# 180_schematic_5_layer.net
KiCad netlist of a schematic drawn in EAGLE
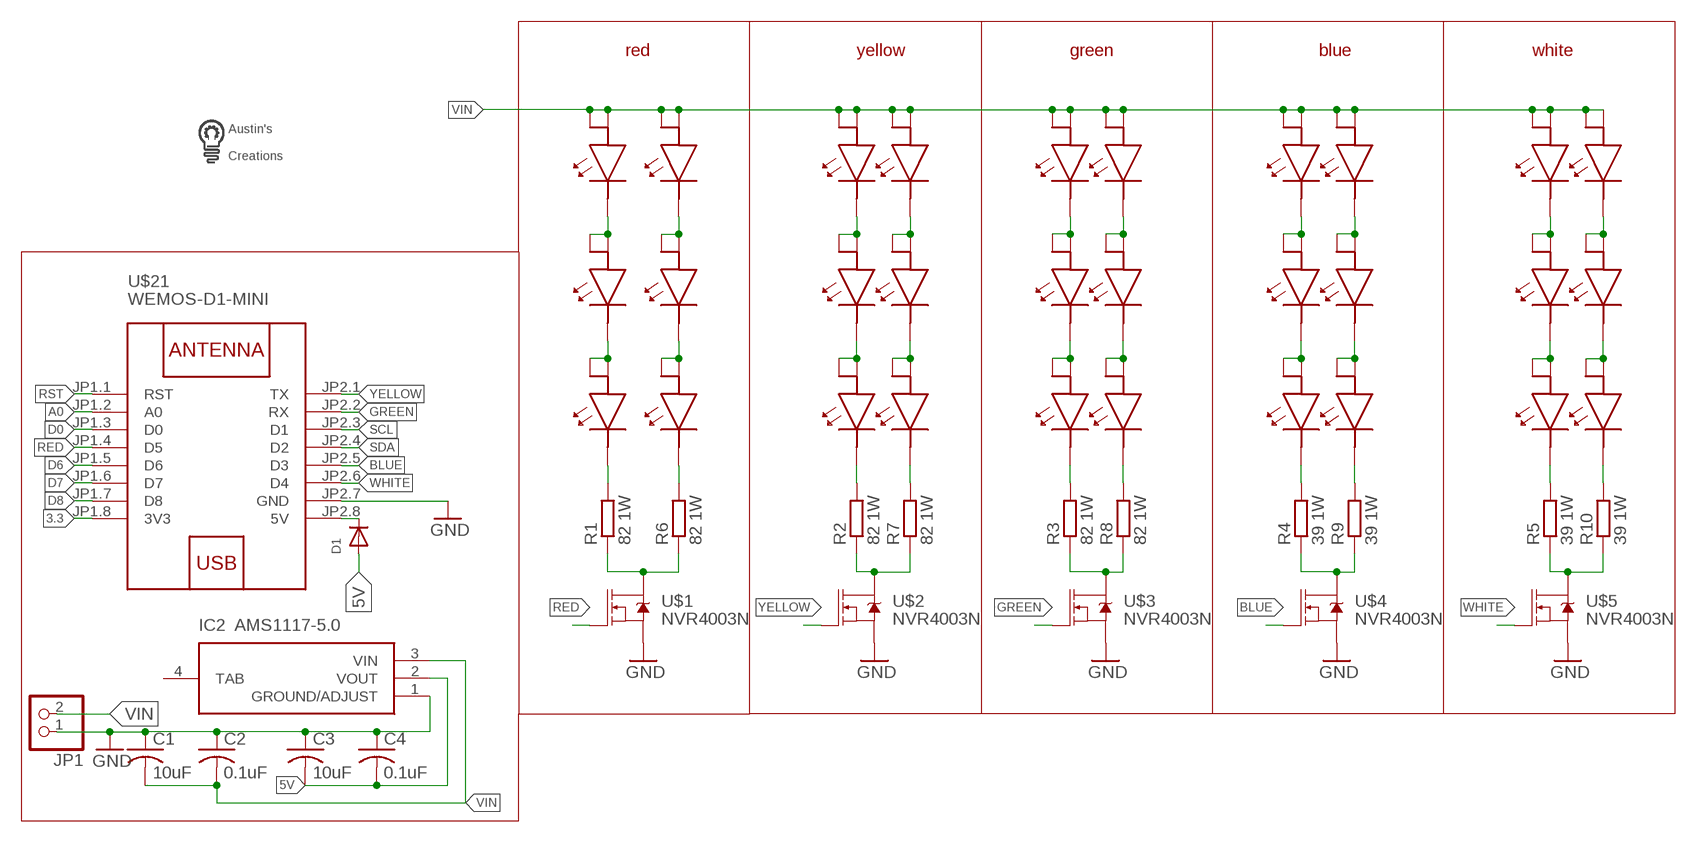
[diagram p0: schematic, sheet 1]

(export (version "E")
  (design (tool "Eeschema 10.0.6"))
  (components
    (comp (ref "C1")
      (value "10uF")
      (footprint "eagle-import:C0603")
      (libsource (lib "eagle-import") (part "C-USC0603"))
    )
    (comp (ref "C2")
      (value "0.1uF")
      (footprint "eagle-import:C0603")
      (libsource (lib "eagle-import") (part "C-USC0603"))
    )
    (comp (ref "C3")
      (value "10uF")
      (footprint "eagle-import:C0603")
      (libsource (lib "eagle-import") (part "C-USC0603"))
    )
    (comp (ref "C4")
      (value "0.1uF")
      (footprint "eagle-import:C0603")
      (libsource (lib "eagle-import") (part "C-USC0603"))
    )
    (comp (ref "D1")
      (value "DIODESOD-123")
      (footprint "eagle-import:SOD-123")
      (libsource (lib "eagle-import") (part "DIODESOD-123"))
    )
    (comp (ref "IC2")
      (value "AMS1117-5.0")
      (footprint "eagle-import:SOT229P700X180-4N")
      (libsource (lib "eagle-import") (part "AMS1117-5.0"))
    )
    (comp (ref "JP1")
      (value "PINHD-1X2")
      (footprint "eagle-import:1X02")
      (libsource (lib "eagle-import") (part "PINHD-1X2"))
    )
    (comp (ref "R1")
      (value "82 1W")
      (footprint "eagle-import:R2010")
      (libsource (lib "eagle-import") (part "R-EU_R2010"))
    )
    (comp (ref "R2")
      (value "82 1W")
      (footprint "eagle-import:R2010")
      (libsource (lib "eagle-import") (part "R-EU_R2010"))
    )
    (comp (ref "R3")
      (value "82 1W")
      (footprint "eagle-import:R2010")
      (libsource (lib "eagle-import") (part "R-EU_R2010"))
    )
    (comp (ref "R4")
      (value "39 1W")
      (footprint "eagle-import:R2010")
      (libsource (lib "eagle-import") (part "R-EU_R2010"))
    )
    (comp (ref "R5")
      (value "39 1W")
      (footprint "eagle-import:R2010")
      (libsource (lib "eagle-import") (part "R-EU_R2010"))
    )
    (comp (ref "R6")
      (value "82 1W")
      (footprint "eagle-import:R2010")
      (libsource (lib "eagle-import") (part "R-EU_R2010"))
    )
    (comp (ref "R7")
      (value "82 1W")
      (footprint "eagle-import:R2010")
      (libsource (lib "eagle-import") (part "R-EU_R2010"))
    )
    (comp (ref "R8")
      (value "82 1W")
      (footprint "eagle-import:R2010")
      (libsource (lib "eagle-import") (part "R-EU_R2010"))
    )
    (comp (ref "R9")
      (value "39 1W")
      (footprint "eagle-import:R2010")
      (libsource (lib "eagle-import") (part "R-EU_R2010"))
    )
    (comp (ref "R10")
      (value "39 1W")
      (footprint "eagle-import:R2010")
      (libsource (lib "eagle-import") (part "R-EU_R2010"))
    )
    (comp (ref "U$1")
      (value "NVR4003N")
      (footprint "eagle-import:SOT23")
      (libsource (lib "eagle-import") (part "NVR4003N"))
    )
    (comp (ref "U$2")
      (value "NVR4003N")
      (footprint "eagle-import:SOT23")
      (libsource (lib "eagle-import") (part "NVR4003N"))
    )
    (comp (ref "U$3")
      (value "NVR4003N")
      (footprint "eagle-import:SOT23")
      (libsource (lib "eagle-import") (part "NVR4003N"))
    )
    (comp (ref "U$4")
      (value "NVR4003N")
      (footprint "eagle-import:SOT23")
      (libsource (lib "eagle-import") (part "NVR4003N"))
    )
    (comp (ref "U$5")
      (value "NVR4003N")
      (footprint "eagle-import:SOT23")
      (libsource (lib "eagle-import") (part "NVR4003N"))
    )
    (comp (ref "U$6")
      (value "5730LED")
      (footprint "eagle-import:5730LED")
      (libsource (lib "eagle-import") (part "5730LED"))
    )
    (comp (ref "U$7")
      (value "5730LED")
      (footprint "eagle-import:5730LED")
      (libsource (lib "eagle-import") (part "5730LED"))
    )
    (comp (ref "U$8")
      (value "5730LED")
      (footprint "eagle-import:5730LED")
      (libsource (lib "eagle-import") (part "5730LED"))
    )
    (comp (ref "U$9")
      (value "5730LED")
      (footprint "eagle-import:5730LED")
      (libsource (lib "eagle-import") (part "5730LED"))
    )
    (comp (ref "U$10")
      (value "5730LED")
      (footprint "eagle-import:5730LED")
      (libsource (lib "eagle-import") (part "5730LED"))
    )
    (comp (ref "U$11")
      (value "5730LED")
      (footprint "eagle-import:5730LED")
      (libsource (lib "eagle-import") (part "5730LED"))
    )
    (comp (ref "U$12")
      (value "5730LED")
      (footprint "eagle-import:5730LED")
      (libsource (lib "eagle-import") (part "5730LED"))
    )
    (comp (ref "U$13")
      (value "5730LED")
      (footprint "eagle-import:5730LED")
      (libsource (lib "eagle-import") (part "5730LED"))
    )
    (comp (ref "U$14")
      (value "5730LED")
      (footprint "eagle-import:5730LED")
      (libsource (lib "eagle-import") (part "5730LED"))
    )
    (comp (ref "U$15")
      (value "5730LED")
      (footprint "eagle-import:5730LED")
      (libsource (lib "eagle-import") (part "5730LED"))
    )
    (comp (ref "U$16")
      (value "5730LED")
      (footprint "eagle-import:5730LED")
      (libsource (lib "eagle-import") (part "5730LED"))
    )
    (comp (ref "U$17")
      (value "5730LED")
      (footprint "eagle-import:5730LED")
      (libsource (lib "eagle-import") (part "5730LED"))
    )
    (comp (ref "U$18")
      (value "5730LED")
      (footprint "eagle-import:5730LED")
      (libsource (lib "eagle-import") (part "5730LED"))
    )
    (comp (ref "U$19")
      (value "5730LED")
      (footprint "eagle-import:5730LED")
      (libsource (lib "eagle-import") (part "5730LED"))
    )
    (comp (ref "U$20")
      (value "5730LED")
      (footprint "eagle-import:5730LED")
      (libsource (lib "eagle-import") (part "5730LED"))
    )
    (comp (ref "U$21")
      (value "WEMOS-D1-MINI")
      (footprint "eagle-import:WEMOS-D1-MINI")
      (libsource (lib "eagle-import") (part "WEMOS-D1-MINI"))
    )
    (comp (ref "U$22")
      (value "LOGO")
      (footprint "eagle-import:LOGO")
      (libsource (lib "eagle-import") (part "LOGO"))
    )
    (comp (ref "U$23")
      (value "5730LED")
      (footprint "eagle-import:5730LED")
      (libsource (lib "eagle-import") (part "5730LED"))
    )
    (comp (ref "U$24")
      (value "5730LED")
      (footprint "eagle-import:5730LED")
      (libsource (lib "eagle-import") (part "5730LED"))
    )
    (comp (ref "U$25")
      (value "5730LED")
      (footprint "eagle-import:5730LED")
      (libsource (lib "eagle-import") (part "5730LED"))
    )
    (comp (ref "U$26")
      (value "5730LED")
      (footprint "eagle-import:5730LED")
      (libsource (lib "eagle-import") (part "5730LED"))
    )
    (comp (ref "U$27")
      (value "5730LED")
      (footprint "eagle-import:5730LED")
      (libsource (lib "eagle-import") (part "5730LED"))
    )
    (comp (ref "U$28")
      (value "5730LED")
      (footprint "eagle-import:5730LED")
      (libsource (lib "eagle-import") (part "5730LED"))
    )
    (comp (ref "U$29")
      (value "5730LED")
      (footprint "eagle-import:5730LED")
      (libsource (lib "eagle-import") (part "5730LED"))
    )
    (comp (ref "U$30")
      (value "5730LED")
      (footprint "eagle-import:5730LED")
      (libsource (lib "eagle-import") (part "5730LED"))
    )
    (comp (ref "U$31")
      (value "5730LED")
      (footprint "eagle-import:5730LED")
      (libsource (lib "eagle-import") (part "5730LED"))
    )
    (comp (ref "U$32")
      (value "5730LED")
      (footprint "eagle-import:5730LED")
      (libsource (lib "eagle-import") (part "5730LED"))
    )
    (comp (ref "U$33")
      (value "5730LED")
      (footprint "eagle-import:5730LED")
      (libsource (lib "eagle-import") (part "5730LED"))
    )
    (comp (ref "U$34")
      (value "5730LED")
      (footprint "eagle-import:5730LED")
      (libsource (lib "eagle-import") (part "5730LED"))
    )
    (comp (ref "U$35")
      (value "5730LED")
      (footprint "eagle-import:5730LED")
      (libsource (lib "eagle-import") (part "5730LED"))
    )
    (comp (ref "U$36")
      (value "5730LED")
      (footprint "eagle-import:5730LED")
      (libsource (lib "eagle-import") (part "5730LED"))
    )
    (comp (ref "U$37")
      (value "5730LED")
      (footprint "eagle-import:5730LED")
      (libsource (lib "eagle-import") (part "5730LED"))
    )
  )
  (nets
    (net (code "1") (name "3.3") (class "Default")
      (node (ref "U$21") (pin "JP1.8") (pinfunction "3V3_JP1.8") (pintype "power_in"))
    )
    (net (code "2") (name "5V") (class "Default")
      (node (ref "C3") (pin "2") (pinfunction "2_2") (pintype "passive"))
      (node (ref "C4") (pin "2") (pinfunction "2_2") (pintype "passive"))
      (node (ref "D1") (pin "A") (pinfunction "A_A") (pintype "passive"))
      (node (ref "IC2") (pin "2") (pinfunction "VOUT_2") (pintype "bidirectional"))
    )
    (net (code "3") (name "A0") (class "Default")
      (node (ref "U$21") (pin "JP1.2") (pinfunction "A0_JP1.2") (pintype "bidirectional"))
    )
    (net (code "4") (name "BLUE") (class "Default")
      (node (ref "U$21") (pin "JP2.5") (pinfunction "D3_JP2.5") (pintype "bidirectional"))
      (node (ref "U$4") (pin "2") (pinfunction "G_2") (pintype "bidirectional"))
    )
    (net (code "5") (name "D0") (class "Default")
      (node (ref "U$21") (pin "JP1.3") (pinfunction "D0_JP1.3") (pintype "bidirectional"))
    )
    (net (code "6") (name "D6") (class "Default")
      (node (ref "U$21") (pin "JP1.5") (pinfunction "D6_JP1.5") (pintype "bidirectional"))
    )
    (net (code "7") (name "D7") (class "Default")
      (node (ref "U$21") (pin "JP1.6") (pinfunction "D7_JP1.6") (pintype "bidirectional"))
    )
    (net (code "8") (name "D8") (class "Default")
      (node (ref "U$21") (pin "JP1.7") (pinfunction "D8_JP1.7") (pintype "bidirectional"))
    )
    (net (code "9") (name "GND") (class "Default")
      (node (ref "C1") (pin "1") (pinfunction "1_1") (pintype "passive"))
      (node (ref "C2") (pin "1") (pinfunction "1_1") (pintype "passive"))
      (node (ref "C3") (pin "1") (pinfunction "1_1") (pintype "passive"))
      (node (ref "C4") (pin "1") (pinfunction "1_1") (pintype "passive"))
      (node (ref "IC2") (pin "1") (pinfunction "GROUND/ADJUST_1") (pintype "bidirectional"))
      (node (ref "JP1") (pin "1") (pinfunction "1_1") (pintype "passive"))
      (node (ref "U$1") (pin "3") (pinfunction "S_3") (pintype "bidirectional"))
      (node (ref "U$2") (pin "3") (pinfunction "S_3") (pintype "bidirectional"))
      (node (ref "U$21") (pin "JP2.7") (pinfunction "GND_JP2.7") (pintype "power_in"))
      (node (ref "U$3") (pin "3") (pinfunction "S_3") (pintype "bidirectional"))
      (node (ref "U$4") (pin "3") (pinfunction "S_3") (pintype "bidirectional"))
      (node (ref "U$5") (pin "3") (pinfunction "S_3") (pintype "bidirectional"))
    )
    (net (code "10") (name "GREEN") (class "Default")
      (node (ref "U$21") (pin "JP2.2") (pinfunction "RX_JP2.2") (pintype "bidirectional"))
      (node (ref "U$3") (pin "2") (pinfunction "G_2") (pintype "bidirectional"))
    )
    (net (code "11") (name "Net-(R1-Pad2)") (class "Default")
      (node (ref "R1") (pin "2") (pinfunction "2_2") (pintype "passive"))
      (node (ref "U$8") (pin "P$2") (pinfunction "P$2_P$2") (pintype "bidirectional"))
    )
    (net (code "12") (name "Net-(R2-Pad2)") (class "Default")
      (node (ref "R2") (pin "2") (pinfunction "2_2") (pintype "passive"))
      (node (ref "U$11") (pin "P$2") (pinfunction "P$2_P$2") (pintype "bidirectional"))
    )
    (net (code "13") (name "Net-(R3-Pad2)") (class "Default")
      (node (ref "R3") (pin "2") (pinfunction "2_2") (pintype "passive"))
      (node (ref "U$14") (pin "P$2") (pinfunction "P$2_P$2") (pintype "bidirectional"))
    )
    (net (code "14") (name "Net-(R4-Pad2)") (class "Default")
      (node (ref "R4") (pin "2") (pinfunction "2_2") (pintype "passive"))
      (node (ref "U$17") (pin "P$2") (pinfunction "P$2_P$2") (pintype "bidirectional"))
    )
    (net (code "15") (name "Net-(R5-Pad2)") (class "Default")
      (node (ref "R5") (pin "2") (pinfunction "2_2") (pintype "passive"))
      (node (ref "U$20") (pin "P$2") (pinfunction "P$2_P$2") (pintype "bidirectional"))
    )
    (net (code "16") (name "Net-(R6-Pad2)") (class "Default")
      (node (ref "R6") (pin "2") (pinfunction "2_2") (pintype "passive"))
      (node (ref "U$25") (pin "P$2") (pinfunction "P$2_P$2") (pintype "bidirectional"))
    )
    (net (code "17") (name "Net-(R7-Pad2)") (class "Default")
      (node (ref "R7") (pin "2") (pinfunction "2_2") (pintype "passive"))
      (node (ref "U$28") (pin "P$2") (pinfunction "P$2_P$2") (pintype "bidirectional"))
    )
    (net (code "18") (name "Net-(R8-Pad2)") (class "Default")
      (node (ref "R8") (pin "2") (pinfunction "2_2") (pintype "passive"))
      (node (ref "U$31") (pin "P$2") (pinfunction "P$2_P$2") (pintype "bidirectional"))
    )
    (net (code "19") (name "Net-(R9-Pad2)") (class "Default")
      (node (ref "R9") (pin "2") (pinfunction "2_2") (pintype "passive"))
      (node (ref "U$34") (pin "P$2") (pinfunction "P$2_P$2") (pintype "bidirectional"))
    )
    (net (code "20") (name "Net-(R10-Pad2)") (class "Default")
      (node (ref "R10") (pin "2") (pinfunction "2_2") (pintype "passive"))
      (node (ref "U$37") (pin "P$2") (pinfunction "P$2_P$2") (pintype "bidirectional"))
    )
    (net (code "21") (name "Net-(U$1-D)") (class "Default")
      (node (ref "R1") (pin "1") (pinfunction "1_1") (pintype "passive"))
      (node (ref "R6") (pin "1") (pinfunction "1_1") (pintype "passive"))
      (node (ref "U$1") (pin "1") (pinfunction "D_1") (pintype "bidirectional"))
    )
    (net (code "22") (name "Net-(U$2-D)") (class "Default")
      (node (ref "R2") (pin "1") (pinfunction "1_1") (pintype "passive"))
      (node (ref "R7") (pin "1") (pinfunction "1_1") (pintype "passive"))
      (node (ref "U$2") (pin "1") (pinfunction "D_1") (pintype "bidirectional"))
    )
    (net (code "23") (name "Net-(U$3-D)") (class "Default")
      (node (ref "R3") (pin "1") (pinfunction "1_1") (pintype "passive"))
      (node (ref "R8") (pin "1") (pinfunction "1_1") (pintype "passive"))
      (node (ref "U$3") (pin "1") (pinfunction "D_1") (pintype "bidirectional"))
    )
    (net (code "24") (name "Net-(U$4-D)") (class "Default")
      (node (ref "R4") (pin "1") (pinfunction "1_1") (pintype "passive"))
      (node (ref "R9") (pin "1") (pinfunction "1_1") (pintype "passive"))
      (node (ref "U$4") (pin "1") (pinfunction "D_1") (pintype "bidirectional"))
    )
    (net (code "25") (name "Net-(U$5-D)") (class "Default")
      (node (ref "R10") (pin "1") (pinfunction "1_1") (pintype "passive"))
      (node (ref "R5") (pin "1") (pinfunction "1_1") (pintype "passive"))
      (node (ref "U$5") (pin "1") (pinfunction "D_1") (pintype "bidirectional"))
    )
    (net (code "26") (name "Net-(U$6-PadP$2)") (class "Default")
      (node (ref "U$6") (pin "P$2") (pinfunction "P$2_P$2") (pintype "bidirectional"))
      (node (ref "U$7") (pin "P$1") (pinfunction "P$1_P$1") (pintype "bidirectional"))
      (node (ref "U$7") (pin "P$3") (pinfunction "P$3_P$3") (pintype "bidirectional"))
    )
    (net (code "27") (name "Net-(U$7-PadP$2)") (class "Default")
      (node (ref "U$7") (pin "P$2") (pinfunction "P$2_P$2") (pintype "bidirectional"))
      (node (ref "U$8") (pin "P$1") (pinfunction "P$1_P$1") (pintype "bidirectional"))
      (node (ref "U$8") (pin "P$3") (pinfunction "P$3_P$3") (pintype "bidirectional"))
    )
    (net (code "28") (name "Net-(U$10-PadP$1)") (class "Default")
      (node (ref "U$10") (pin "P$1") (pinfunction "P$1_P$1") (pintype "bidirectional"))
      (node (ref "U$10") (pin "P$3") (pinfunction "P$3_P$3") (pintype "bidirectional"))
      (node (ref "U$9") (pin "P$2") (pinfunction "P$2_P$2") (pintype "bidirectional"))
    )
    (net (code "29") (name "Net-(U$10-PadP$2)") (class "Default")
      (node (ref "U$10") (pin "P$2") (pinfunction "P$2_P$2") (pintype "bidirectional"))
      (node (ref "U$11") (pin "P$1") (pinfunction "P$1_P$1") (pintype "bidirectional"))
      (node (ref "U$11") (pin "P$3") (pinfunction "P$3_P$3") (pintype "bidirectional"))
    )
    (net (code "30") (name "Net-(U$12-PadP$2)") (class "Default")
      (node (ref "U$12") (pin "P$2") (pinfunction "P$2_P$2") (pintype "bidirectional"))
      (node (ref "U$13") (pin "P$1") (pinfunction "P$1_P$1") (pintype "bidirectional"))
      (node (ref "U$13") (pin "P$3") (pinfunction "P$3_P$3") (pintype "bidirectional"))
    )
    (net (code "31") (name "Net-(U$13-PadP$2)") (class "Default")
      (node (ref "U$13") (pin "P$2") (pinfunction "P$2_P$2") (pintype "bidirectional"))
      (node (ref "U$14") (pin "P$1") (pinfunction "P$1_P$1") (pintype "bidirectional"))
      (node (ref "U$14") (pin "P$3") (pinfunction "P$3_P$3") (pintype "bidirectional"))
    )
    (net (code "32") (name "Net-(U$15-PadP$2)") (class "Default")
      (node (ref "U$15") (pin "P$2") (pinfunction "P$2_P$2") (pintype "bidirectional"))
      (node (ref "U$16") (pin "P$1") (pinfunction "P$1_P$1") (pintype "bidirectional"))
      (node (ref "U$16") (pin "P$3") (pinfunction "P$3_P$3") (pintype "bidirectional"))
    )
    (net (code "33") (name "Net-(U$16-PadP$2)") (class "Default")
      (node (ref "U$16") (pin "P$2") (pinfunction "P$2_P$2") (pintype "bidirectional"))
      (node (ref "U$17") (pin "P$1") (pinfunction "P$1_P$1") (pintype "bidirectional"))
      (node (ref "U$17") (pin "P$3") (pinfunction "P$3_P$3") (pintype "bidirectional"))
    )
    (net (code "34") (name "Net-(U$18-PadP$2)") (class "Default")
      (node (ref "U$18") (pin "P$2") (pinfunction "P$2_P$2") (pintype "bidirectional"))
      (node (ref "U$19") (pin "P$1") (pinfunction "P$1_P$1") (pintype "bidirectional"))
      (node (ref "U$19") (pin "P$3") (pinfunction "P$3_P$3") (pintype "bidirectional"))
    )
    (net (code "35") (name "Net-(U$19-PadP$2)") (class "Default")
      (node (ref "U$19") (pin "P$2") (pinfunction "P$2_P$2") (pintype "bidirectional"))
      (node (ref "U$20") (pin "P$1") (pinfunction "P$1_P$1") (pintype "bidirectional"))
      (node (ref "U$20") (pin "P$3") (pinfunction "P$3_P$3") (pintype "bidirectional"))
    )
    (net (code "36") (name "Net-(U$21-5V)") (class "Default")
      (node (ref "D1") (pin "C") (pinfunction "C_C") (pintype "passive"))
      (node (ref "U$21") (pin "JP2.8") (pinfunction "5V_JP2.8") (pintype "power_in"))
    )
    (net (code "37") (name "Net-(U$23-PadP$2)") (class "Default")
      (node (ref "U$23") (pin "P$2") (pinfunction "P$2_P$2") (pintype "bidirectional"))
      (node (ref "U$24") (pin "P$1") (pinfunction "P$1_P$1") (pintype "bidirectional"))
      (node (ref "U$24") (pin "P$3") (pinfunction "P$3_P$3") (pintype "bidirectional"))
    )
    (net (code "38") (name "Net-(U$24-PadP$2)") (class "Default")
      (node (ref "U$24") (pin "P$2") (pinfunction "P$2_P$2") (pintype "bidirectional"))
      (node (ref "U$25") (pin "P$1") (pinfunction "P$1_P$1") (pintype "bidirectional"))
      (node (ref "U$25") (pin "P$3") (pinfunction "P$3_P$3") (pintype "bidirectional"))
    )
    (net (code "39") (name "Net-(U$26-PadP$2)") (class "Default")
      (node (ref "U$26") (pin "P$2") (pinfunction "P$2_P$2") (pintype "bidirectional"))
      (node (ref "U$27") (pin "P$1") (pinfunction "P$1_P$1") (pintype "bidirectional"))
      (node (ref "U$27") (pin "P$3") (pinfunction "P$3_P$3") (pintype "bidirectional"))
    )
    (net (code "40") (name "Net-(U$27-PadP$2)") (class "Default")
      (node (ref "U$27") (pin "P$2") (pinfunction "P$2_P$2") (pintype "bidirectional"))
      (node (ref "U$28") (pin "P$1") (pinfunction "P$1_P$1") (pintype "bidirectional"))
      (node (ref "U$28") (pin "P$3") (pinfunction "P$3_P$3") (pintype "bidirectional"))
    )
    (net (code "41") (name "Net-(U$29-PadP$2)") (class "Default")
      (node (ref "U$29") (pin "P$2") (pinfunction "P$2_P$2") (pintype "bidirectional"))
      (node (ref "U$30") (pin "P$1") (pinfunction "P$1_P$1") (pintype "bidirectional"))
      (node (ref "U$30") (pin "P$3") (pinfunction "P$3_P$3") (pintype "bidirectional"))
    )
    (net (code "42") (name "Net-(U$30-PadP$2)") (class "Default")
      (node (ref "U$30") (pin "P$2") (pinfunction "P$2_P$2") (pintype "bidirectional"))
      (node (ref "U$31") (pin "P$1") (pinfunction "P$1_P$1") (pintype "bidirectional"))
      (node (ref "U$31") (pin "P$3") (pinfunction "P$3_P$3") (pintype "bidirectional"))
    )
    (net (code "43") (name "Net-(U$32-PadP$2)") (class "Default")
      (node (ref "U$32") (pin "P$2") (pinfunction "P$2_P$2") (pintype "bidirectional"))
      (node (ref "U$33") (pin "P$1") (pinfunction "P$1_P$1") (pintype "bidirectional"))
      (node (ref "U$33") (pin "P$3") (pinfunction "P$3_P$3") (pintype "bidirectional"))
    )
    (net (code "44") (name "Net-(U$33-PadP$2)") (class "Default")
      (node (ref "U$33") (pin "P$2") (pinfunction "P$2_P$2") (pintype "bidirectional"))
      (node (ref "U$34") (pin "P$1") (pinfunction "P$1_P$1") (pintype "bidirectional"))
      (node (ref "U$34") (pin "P$3") (pinfunction "P$3_P$3") (pintype "bidirectional"))
    )
    (net (code "45") (name "Net-(U$35-PadP$2)") (class "Default")
      (node (ref "U$35") (pin "P$2") (pinfunction "P$2_P$2") (pintype "bidirectional"))
      (node (ref "U$36") (pin "P$1") (pinfunction "P$1_P$1") (pintype "bidirectional"))
      (node (ref "U$36") (pin "P$3") (pinfunction "P$3_P$3") (pintype "bidirectional"))
    )
    (net (code "46") (name "Net-(U$36-PadP$2)") (class "Default")
      (node (ref "U$36") (pin "P$2") (pinfunction "P$2_P$2") (pintype "bidirectional"))
      (node (ref "U$37") (pin "P$1") (pinfunction "P$1_P$1") (pintype "bidirectional"))
      (node (ref "U$37") (pin "P$3") (pinfunction "P$3_P$3") (pintype "bidirectional"))
    )
    (net (code "47") (name "RED") (class "Default")
      (node (ref "U$1") (pin "2") (pinfunction "G_2") (pintype "bidirectional"))
      (node (ref "U$21") (pin "JP1.4") (pinfunction "D5_JP1.4") (pintype "bidirectional"))
    )
    (net (code "48") (name "RST") (class "Default")
      (node (ref "U$21") (pin "JP1.1") (pinfunction "RST_JP1.1") (pintype "bidirectional"))
    )
    (net (code "49") (name "SCL") (class "Default")
      (node (ref "U$21") (pin "JP2.3") (pinfunction "D1_JP2.3") (pintype "bidirectional"))
    )
    (net (code "50") (name "SDA") (class "Default")
      (node (ref "U$21") (pin "JP2.4") (pinfunction "D2_JP2.4") (pintype "bidirectional"))
    )
    (net (code "51") (name "VIN") (class "Default")
      (node (ref "C1") (pin "2") (pinfunction "2_2") (pintype "passive"))
      (node (ref "C2") (pin "2") (pinfunction "2_2") (pintype "passive"))
      (node (ref "IC2") (pin "3") (pinfunction "VIN_3") (pintype "bidirectional"))
      (node (ref "JP1") (pin "2") (pinfunction "2_2") (pintype "passive"))
      (node (ref "U$12") (pin "P$1") (pinfunction "P$1_P$1") (pintype "bidirectional"))
      (node (ref "U$12") (pin "P$3") (pinfunction "P$3_P$3") (pintype "bidirectional"))
      (node (ref "U$15") (pin "P$1") (pinfunction "P$1_P$1") (pintype "bidirectional"))
      (node (ref "U$15") (pin "P$3") (pinfunction "P$3_P$3") (pintype "bidirectional"))
      (node (ref "U$18") (pin "P$1") (pinfunction "P$1_P$1") (pintype "bidirectional"))
      (node (ref "U$18") (pin "P$3") (pinfunction "P$3_P$3") (pintype "bidirectional"))
      (node (ref "U$23") (pin "P$1") (pinfunction "P$1_P$1") (pintype "bidirectional"))
      (node (ref "U$23") (pin "P$3") (pinfunction "P$3_P$3") (pintype "bidirectional"))
      (node (ref "U$26") (pin "P$1") (pinfunction "P$1_P$1") (pintype "bidirectional"))
      (node (ref "U$26") (pin "P$3") (pinfunction "P$3_P$3") (pintype "bidirectional"))
      (node (ref "U$29") (pin "P$1") (pinfunction "P$1_P$1") (pintype "bidirectional"))
      (node (ref "U$29") (pin "P$3") (pinfunction "P$3_P$3") (pintype "bidirectional"))
      (node (ref "U$32") (pin "P$1") (pinfunction "P$1_P$1") (pintype "bidirectional"))
      (node (ref "U$32") (pin "P$3") (pinfunction "P$3_P$3") (pintype "bidirectional"))
      (node (ref "U$35") (pin "P$1") (pinfunction "P$1_P$1") (pintype "bidirectional"))
      (node (ref "U$35") (pin "P$3") (pinfunction "P$3_P$3") (pintype "bidirectional"))
      (node (ref "U$6") (pin "P$1") (pinfunction "P$1_P$1") (pintype "bidirectional"))
      (node (ref "U$6") (pin "P$3") (pinfunction "P$3_P$3") (pintype "bidirectional"))
      (node (ref "U$9") (pin "P$1") (pinfunction "P$1_P$1") (pintype "bidirectional"))
      (node (ref "U$9") (pin "P$3") (pinfunction "P$3_P$3") (pintype "bidirectional"))
    )
    (net (code "52") (name "WHITE") (class "Default")
      (node (ref "U$21") (pin "JP2.6") (pinfunction "D4_JP2.6") (pintype "bidirectional"))
      (node (ref "U$5") (pin "2") (pinfunction "G_2") (pintype "bidirectional"))
    )
    (net (code "53") (name "YELLOW") (class "Default")
      (node (ref "U$2") (pin "2") (pinfunction "G_2") (pintype "bidirectional"))
      (node (ref "U$21") (pin "JP2.1") (pinfunction "TX_JP2.1") (pintype "bidirectional"))
    )
    (net (code "54") (name "unconnected-(IC2-TAB-Pad4)") (class "Default")
      (node (ref "IC2") (pin "4") (pinfunction "TAB_4") (pintype "bidirectional"))
    )
  )
)
